# multilayer.net
KiCad netlist of a schematic drawn in Altium Designer
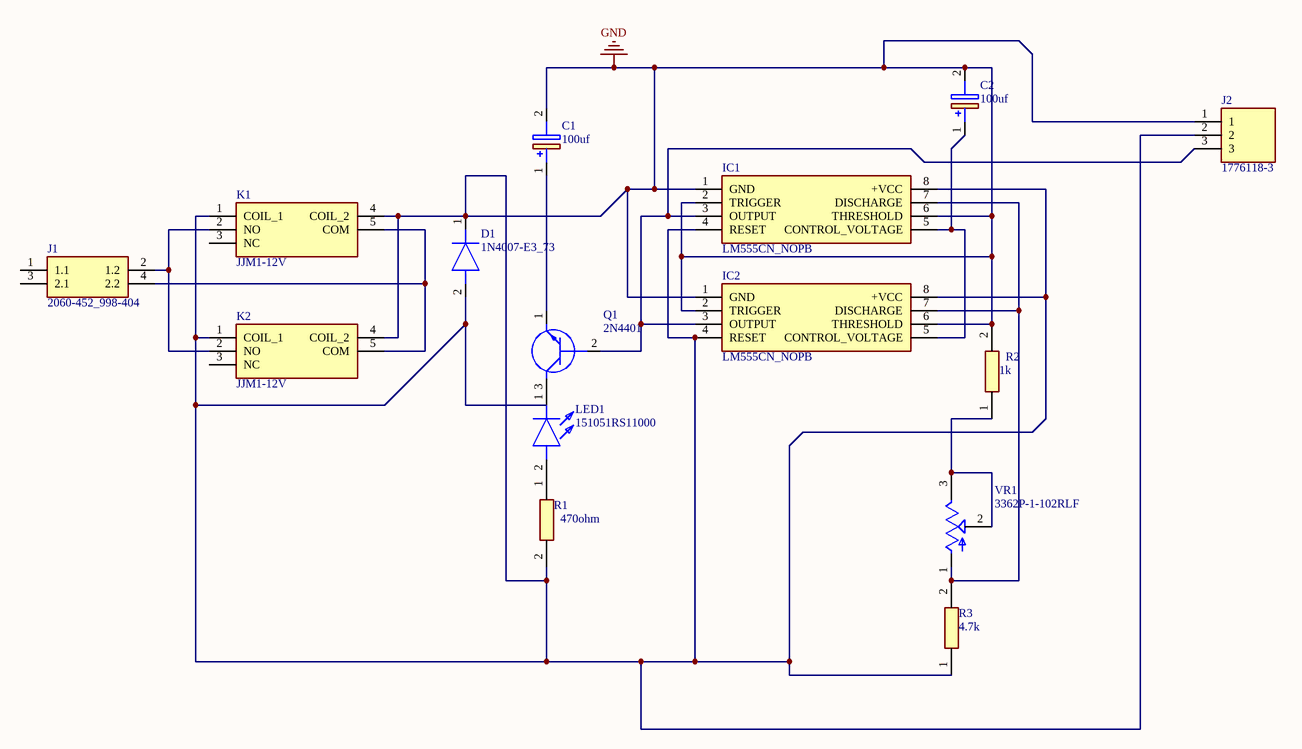
[diagram p0: multilayer.SchDoc]

(export (version "E")
  (design (tool "Eeschema 10.0.6"))
  (components
    (comp (ref "C1")
      (value "100uf")
      (footprint "SamacSys:CAPPRD500W65D1000H3200")
      (description "Capacitor Polarised")
      (fields
        (field (name "MANUFACTURER_PART_NUMBER") "EEU-FC2A101L")
        (field (name "MOUSER PART NUMBER") "667-EEU-FC2A101L")
      )
      (libsource (lib "*") (part "EEU-FC2A101L"))
    )
    (comp (ref "C2")
      (value "100uf")
      (footprint "SamacSys:CAPPRD500W65D1000H3200")
      (description "Capacitor Polarised")
      (fields
        (field (name "MANUFACTURER_PART_NUMBER") "EEU-FC2A101L")
        (field (name "MOUSER PART NUMBER") "667-EEU-FC2A101L")
      )
      (libsource (lib "*") (part "EEU-FC2A101L"))
    )
    (comp (ref "D1")
      (value "1N4007-E3_73")
      (footprint "SamacSys:DIOAD1405W86L465D235")
      (description "Diode")
      (fields
        (field (name "MANUFACTURER_PART_NUMBER") "1N4007-E3/73")
        (field (name "MOUSER PART NUMBER") "625-1N4007-E3/73")
      )
      (libsource (lib "*") (part "1N4007-E3_73"))
    )
    (comp (ref "IC1")
      (value "LM555CN_NOPB")
      (footprint "SamacSys:DIP794W53P254L959H508Q8N")
      (description "Integrated Circuit")
      (fields
        (field (name "MANUFACTURER_PART_NUMBER") "LM555CN/NOPB")
        (field (name "MOUSER PART NUMBER") "926-LM555CN/NOPB")
      )
      (libsource (lib "*") (part "LM555CN_NOPB"))
    )
    (comp (ref "IC2")
      (value "LM555CN_NOPB")
      (footprint "SamacSys:DIP794W53P254L959H508Q8N")
      (description "Integrated Circuit")
      (fields
        (field (name "MANUFACTURER_PART_NUMBER") "LM555CN/NOPB")
        (field (name "MOUSER PART NUMBER") "926-LM555CN/NOPB")
      )
      (libsource (lib "*") (part "LM555CN_NOPB"))
    )
    (comp (ref "J1")
      (value "2060-452_998-404")
      (footprint "SamacSys:2060452998404")
      (description "Connector")
      (fields (field (name "MANUFACTURER_PART_NUMBER") "2060-452/998-404"))
      (libsource (lib "*") (part "2060-452_998-404"))
    )
    (comp (ref "J2")
      (value "1776118-3")
      (footprint "TE_1776118-3")
      (description "Conn Terminal Block F 3 POS 5mm Solder ST Thru-Hole Package")
      (fields (field (name "MF") "TE Connectivity"))
      (libsource (lib "1776118-3") (part "1776118-3"))
    )
    (comp (ref "K1")
      (value "JJM1-12V")
      (footprint "SamacSys:JJM112V")
      (description "Relay or Contactor")
      (fields (field (name "MOUSER PART NUMBER") "769-JJM1-12V"))
      (libsource (lib "*") (part "JJM1-12V"))
    )
    (comp (ref "K2")
      (value "JJM1-12V")
      (footprint "SamacSys:JJM112V")
      (description "Relay or Contactor")
      (fields (field (name "MOUSER PART NUMBER") "769-JJM1-12V"))
      (libsource (lib "*") (part "JJM1-12V"))
    )
    (comp (ref "LED1")
      (value "151051RS11000")
      (footprint "SamacSys:151051RS11000")
      (description "LED")
      (fields (field (name "MOUSER PART NUMBER") "710-151051RS11000"))
      (libsource (lib "*") (part "151051RS11000"))
    )
    (comp (ref "Q1")
      (value "2N4401")
      (footprint "SamacSys:CS_TO-92")
      (description "Transistor BJT NPN")
      (fields (field (name "MOUSER PART NUMBER") "610-2N4401"))
      (libsource (lib "*") (part "2N4401"))
    )
    (comp (ref "R1")
      (value "470ohm")
      (footprint "SamacSys:RESAD1987W56L1031D239")
      (description "Resistor")
      (fields
        (field (name "MANUFACTURER_PART_NUMBER") "RS01A1R000FE12")
        (field (name "MOUSER PART NUMBER") "71-RS01A1R000FE12")
      )
      (libsource (lib "SamacSys") (part "RS01A1R000FE12"))
    )
    (comp (ref "R2")
      (value "1k")
      (footprint "SamacSys:RESAD1987W56L1031D239")
      (description "Resistor")
      (fields
        (field (name "MANUFACTURER_PART_NUMBER") "RS01A1R000FE12")
        (field (name "MOUSER PART NUMBER") "71-RS01A1R000FE12")
      )
      (libsource (lib "") (part "RS01A1R000FE12_1"))
    )
    (comp (ref "R3")
      (value "4.7k")
      (footprint "SamacSys:RESAD1987W56L1031D239")
      (description "Resistor")
      (fields
        (field (name "MANUFACTURER_PART_NUMBER") "RS01A1R000FE12")
        (field (name "MOUSER PART NUMBER") "71-RS01A1R000FE12")
      )
      (libsource (lib "") (part "RS01A1R000FE12_1"))
    )
    (comp (ref "VR1")
      (value "3362P-1-102RLF")
      (footprint "TRIM_3362P-1-102RLF")
      (description "1 kOhms 0.5W, 1/2W PC Pins Through Hole Trimmer Potentiometer Cermet 1 Turn Top Adjustment")
      (fields (field (name "MF") "Bourns"))
      (libsource (lib "3362P-1-102RLF") (part "3362P-1-102RLF"))
    )
  )
  (nets
    (net (code "1") (name "GND") (class "Default")
      (node (ref "C1") (pin "2") (pinfunction "-_2") (pintype "passive"))
      (node (ref "C2") (pin "2") (pinfunction "-_2") (pintype "passive"))
      (node (ref "D1") (pin "1") (pinfunction "K_1") (pintype "passive"))
      (node (ref "D1") (pin "2") (pinfunction "A_2") (pintype "passive"))
      (node (ref "IC1") (pin "1") (pinfunction "GND_1") (pintype "passive"))
      (node (ref "IC1") (pin "2") (pinfunction "TRIGGER_2") (pintype "passive"))
      (node (ref "IC1") (pin "4") (pinfunction "RESET_4") (pintype "passive"))
      (node (ref "IC1") (pin "6") (pinfunction "THRESHOLD_6") (pintype "passive"))
      (node (ref "IC1") (pin "8") (pinfunction "+VCC_8") (pintype "passive"))
      (node (ref "IC2") (pin "1") (pinfunction "GND_1") (pintype "passive"))
      (node (ref "IC2") (pin "2") (pinfunction "TRIGGER_2") (pintype "passive"))
      (node (ref "IC2") (pin "4") (pinfunction "RESET_4") (pintype "passive"))
      (node (ref "IC2") (pin "6") (pinfunction "THRESHOLD_6") (pintype "passive"))
      (node (ref "IC2") (pin "8") (pinfunction "+VCC_8") (pintype "passive"))
      (node (ref "J2") (pin "1") (pinfunction "1_1") (pintype "passive"))
      (node (ref "J2") (pin "2") (pinfunction "2_2") (pintype "passive"))
      (node (ref "K1") (pin "1") (pinfunction "COIL_1_1") (pintype "passive"))
      (node (ref "K1") (pin "4") (pinfunction "COIL_2_4") (pintype "passive"))
      (node (ref "K2") (pin "1") (pinfunction "COIL_1_1") (pintype "passive"))
      (node (ref "K2") (pin "4") (pinfunction "COIL_2_4") (pintype "passive"))
      (node (ref "R1") (pin "2") (pinfunction "2_2") (pintype "passive"))
      (node (ref "R2") (pin "2") (pinfunction "2_2") (pintype "passive"))
      (node (ref "R3") (pin "1") (pinfunction "1_1") (pintype "passive"))
    )
    (net (code "2") (name "Net-(C1-+)") (class "Default")
      (node (ref "C1") (pin "1") (pinfunction "+_1") (pintype "passive"))
      (node (ref "Q1") (pin "1") (pinfunction "E_1") (pintype "passive"))
    )
    (net (code "3") (name "Net-(C2-+)") (class "Default")
      (node (ref "C2") (pin "1") (pinfunction "+_1") (pintype "passive"))
      (node (ref "IC1") (pin "5") (pinfunction "CONTROL_VOLTAGE_5") (pintype "passive"))
      (node (ref "IC2") (pin "5") (pinfunction "CONTROL_VOLTAGE_5") (pintype "passive"))
    )
    (net (code "4") (name "Net-(IC1-DISCHARGE)") (class "Default")
      (node (ref "IC1") (pin "7") (pinfunction "DISCHARGE_7") (pintype "passive"))
      (node (ref "IC2") (pin "7") (pinfunction "DISCHARGE_7") (pintype "passive"))
      (node (ref "R3") (pin "2") (pinfunction "2_2") (pintype "passive"))
      (node (ref "VR1") (pin "1") (pinfunction "CCW_1") (pintype "passive"))
    )
    (net (code "5") (name "Net-(IC1-OUTPUT)") (class "Default")
      (node (ref "IC1") (pin "3") (pinfunction "OUTPUT_3") (pintype "passive"))
      (node (ref "IC2") (pin "3") (pinfunction "OUTPUT_3") (pintype "passive"))
      (node (ref "J2") (pin "3") (pinfunction "3_3") (pintype "passive"))
      (node (ref "Q1") (pin "2") (pinfunction "B_2") (pintype "passive"))
    )
    (net (code "6") (name "Net-(J1-1.2)") (class "Default")
      (node (ref "J1") (pin "2") (pinfunction "1.2_2") (pintype "passive"))
      (node (ref "K1") (pin "2") (pinfunction "NO_2") (pintype "passive"))
      (node (ref "K2") (pin "2") (pinfunction "NO_2") (pintype "passive"))
    )
    (net (code "7") (name "Net-(J1-2.2)") (class "Default")
      (node (ref "J1") (pin "4") (pinfunction "2.2_4") (pintype "passive"))
      (node (ref "K1") (pin "5") (pinfunction "COM_5") (pintype "passive"))
      (node (ref "K2") (pin "5") (pinfunction "COM_5") (pintype "passive"))
    )
    (net (code "8") (name "Net-(LED1-A)") (class "Default")
      (node (ref "LED1") (pin "2") (pinfunction "A_2") (pintype "passive"))
      (node (ref "R1") (pin "1") (pinfunction "1_1") (pintype "passive"))
    )
    (net (code "9") (name "Net-(LED1-K)") (class "Default")
      (node (ref "LED1") (pin "1") (pinfunction "K_1") (pintype "passive"))
      (node (ref "Q1") (pin "3") (pinfunction "C_3") (pintype "passive"))
    )
    (net (code "10") (name "Net-(VR1-CW)") (class "Default")
      (node (ref "R2") (pin "1") (pinfunction "1_1") (pintype "passive"))
      (node (ref "VR1") (pin "2") (pinfunction "WIPER_2") (pintype "passive"))
      (node (ref "VR1") (pin "3") (pinfunction "CW_3") (pintype "passive"))
    )
    (net (code "11") (name "unconnected-(J1-1.1-Pad1)") (class "Default")
      (node (ref "J1") (pin "1") (pinfunction "1.1_1") (pintype "passive"))
    )
    (net (code "12") (name "unconnected-(J1-2.1-Pad3)") (class "Default")
      (node (ref "J1") (pin "3") (pinfunction "2.1_3") (pintype "passive"))
    )
    (net (code "13") (name "unconnected-(K1-NC-Pad3)") (class "Default")
      (node (ref "K1") (pin "3") (pinfunction "NC_3") (pintype "passive"))
    )
    (net (code "14") (name "unconnected-(K2-NC-Pad3)") (class "Default")
      (node (ref "K2") (pin "3") (pinfunction "NC_3") (pintype "passive"))
    )
  )
)
